# UFP.net
KiCad netlist of a schematic drawn in Altium Designer
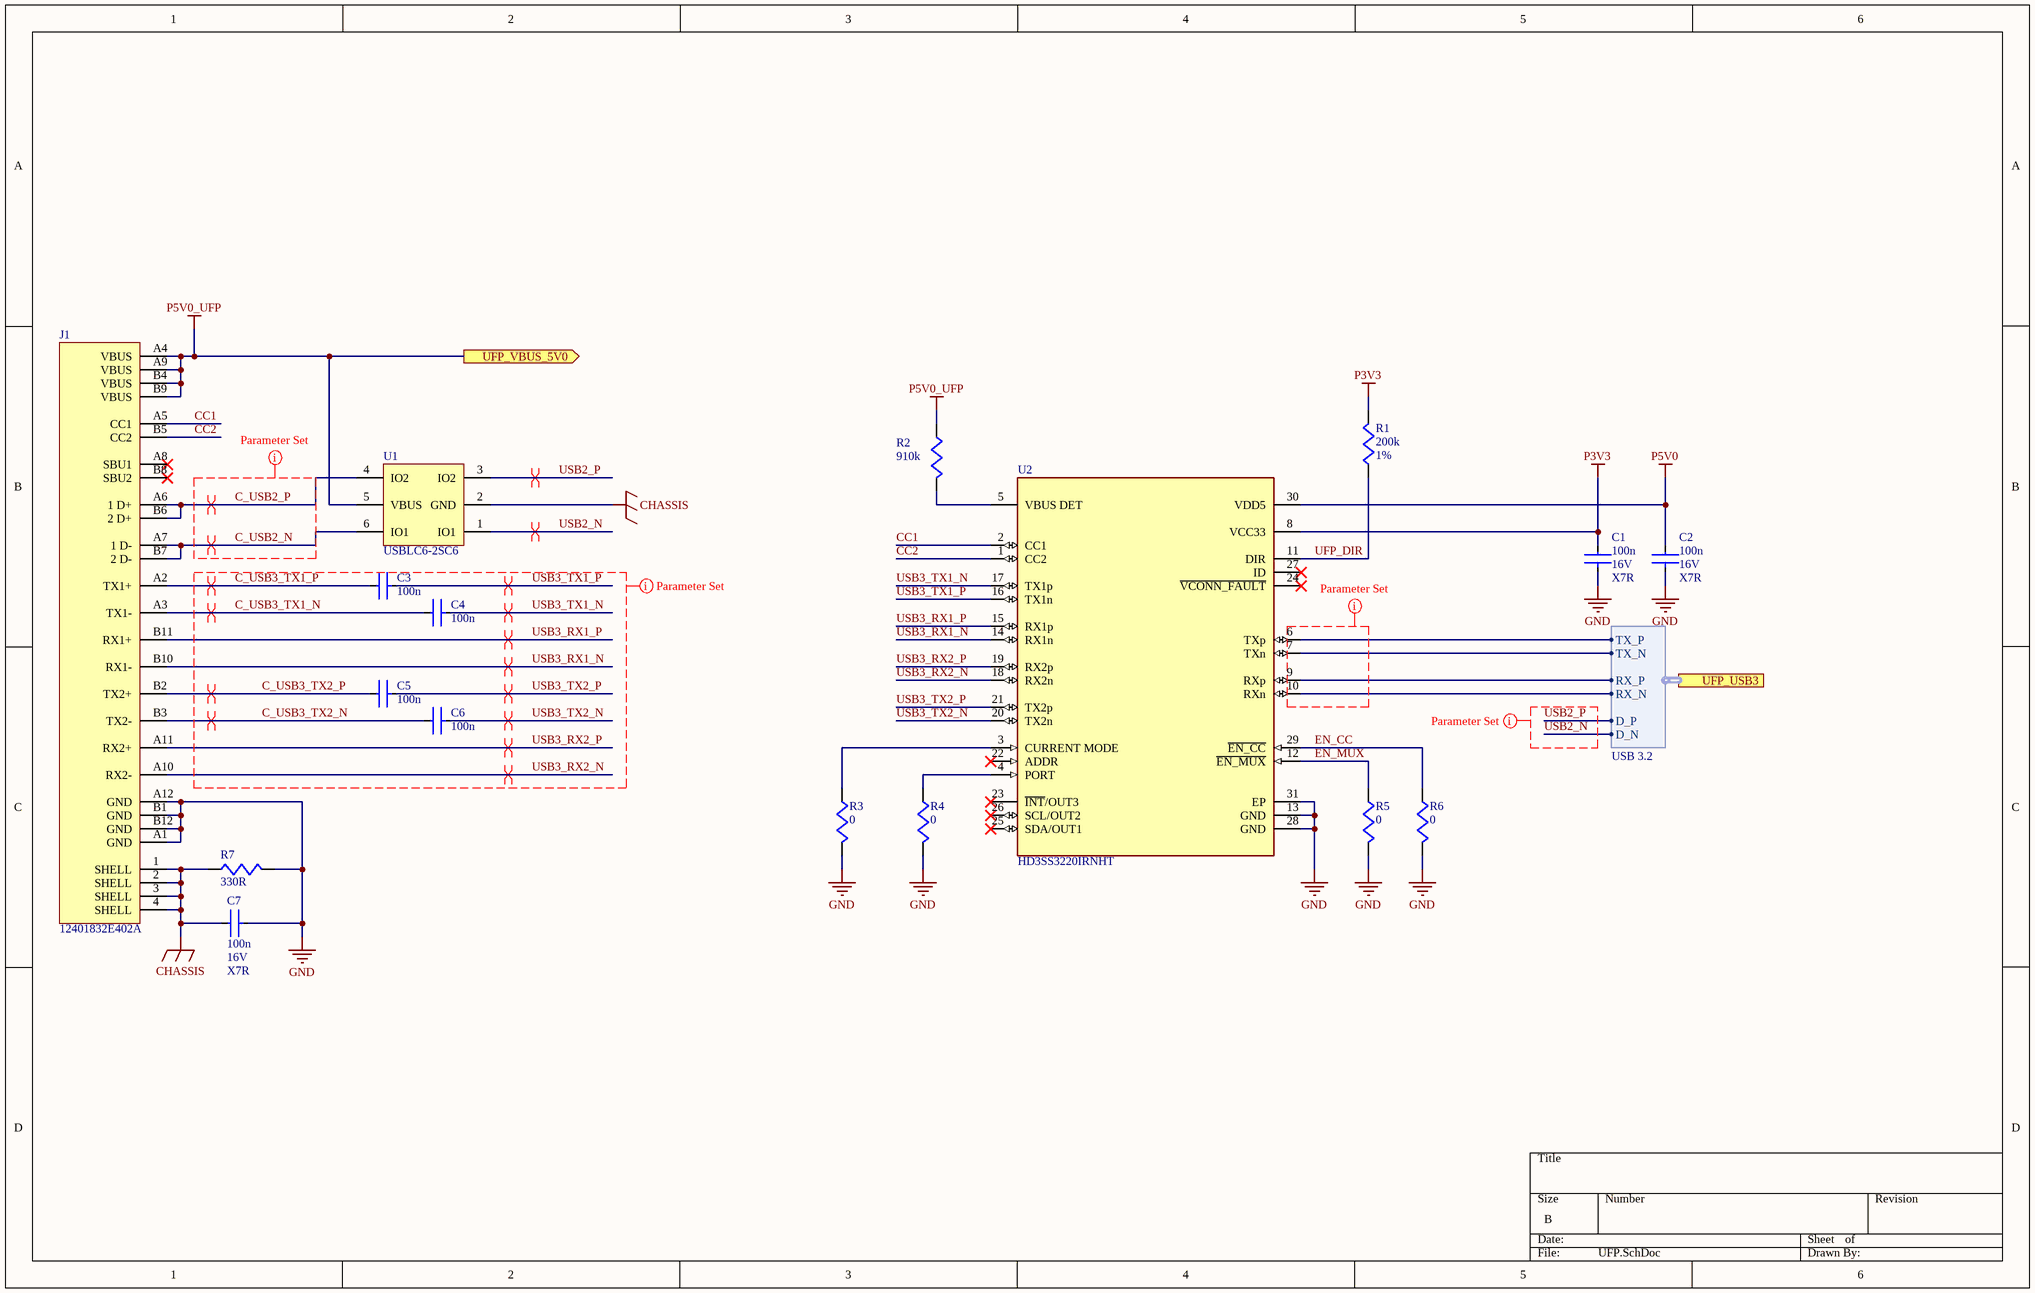
[diagram p0: UFP.SchDoc]

(export (version "E")
  (design (tool "Eeschema 10.0.6"))
  (components
    (comp (ref "C1")
      (value "100n")
      (footprint "CAPC1005X06N")
      (description "16V 100nF X7R ±10% 0402 Multilayer Ceramic Capacitors MLCC - SMD/SMT ROHS")
      (fields
        (field (name "VOLTAGE") "16V")
        (field (name "DIELECTRIC") "X7R")
        (field (name "LCSC PART #") "C1525")
        (field (name "Comment") "100nF 16V 0402")
      )
      (libsource (lib "CWRU Motorsports") (part "Capacitor"))
    )
    (comp (ref "C2")
      (value "100n")
      (footprint "CAPC1005X06N")
      (description "16V 100nF X7R ±10% 0402 Multilayer Ceramic Capacitors MLCC - SMD/SMT ROHS")
      (fields
        (field (name "VOLTAGE") "16V")
        (field (name "DIELECTRIC") "X7R")
        (field (name "LCSC PART #") "C1525")
        (field (name "Comment") "100nF 16V 0402")
      )
      (libsource (lib "CWRU Motorsports") (part "Capacitor"))
    )
    (comp (ref "C3")
      (value "100n")
      (footprint "CAPC0603X03N")
      (description "10V 100nF X5R ±10% 0201 Multilayer Ceramic Capacitors MLCC - SMD/SMT ROHS")
      (fields (field (name "VOLTAGE") "10V") (field (name "LCSC PART #") "C76934"))
      (libsource (lib "CWRU Motorsports") (part "Capacitor"))
    )
    (comp (ref "C4")
      (value "100n")
      (footprint "CAPC0603X03N")
      (description "10V 100nF X5R ±10% 0201 Multilayer Ceramic Capacitors MLCC - SMD/SMT ROHS")
      (fields (field (name "VOLTAGE") "10V") (field (name "LCSC PART #") "C76934"))
      (libsource (lib "CWRU Motorsports") (part "Capacitor"))
    )
    (comp (ref "C5")
      (value "100n")
      (footprint "CAPC0603X03N")
      (description "10V 100nF X5R ±10% 0201 Multilayer Ceramic Capacitors MLCC - SMD/SMT ROHS")
      (fields (field (name "VOLTAGE") "10V") (field (name "LCSC PART #") "C76934"))
      (libsource (lib "CWRU Motorsports") (part "Capacitor"))
    )
    (comp (ref "C6")
      (value "100n")
      (footprint "CAPC0603X03N")
      (description "10V 100nF X5R ±10% 0201 Multilayer Ceramic Capacitors MLCC - SMD/SMT ROHS")
      (fields (field (name "VOLTAGE") "10V") (field (name "LCSC PART #") "C76934"))
      (libsource (lib "CWRU Motorsports") (part "Capacitor"))
    )
    (comp (ref "C7")
      (value "100n")
      (footprint "CAPC1005X06N")
      (description "16V 100nF X7R ±10% 0402 Multilayer Ceramic Capacitors MLCC - SMD/SMT ROHS")
      (fields
        (field (name "VOLTAGE") "16V")
        (field (name "DIELECTRIC") "X7R")
        (field (name "LCSC PART #") "C1525")
        (field (name "Comment") "100nF 16V 0402")
      )
      (libsource (lib "CWRU Motorsports") (part "Capacitor"))
    )
    (comp (ref "J1")
      (value "12401832E402A")
      (footprint "FP-12401832E402A-MFG")
      (description "Conn USB Type C RCP 24 POS 0.25mm Solder RA SMD 24 Terminal 1 Port T/R")
      (fields (field (name "LCSC PART #") "C464604"))
      (libsource (lib "CWRU Motorsports") (part "50854493bfec571c3c083d899a0df29"))
    )
    (comp (ref "R1")
      (value "200k")
      (footprint "RESC1005X04M")
      (description "62.5mW Thick Film Resistors 50V ±100ppm/℃ ±1% 200kΩ 0402 Chip Resistor - Surface Mount ROHS")
      (fields
        (field (name "TOLERANCE") "1%")
        (field (name "LCSC PART #") "C114763")
        (field (name "Comment") "200k 1% 0402")
      )
      (libsource (lib "CWRU Motorsports") (part "Resistor"))
    )
    (comp (ref "R2")
      (value "910k")
      (footprint "RESC1005X04M")
      (description "62.5mW Thick Film Resistors 50V ±100ppm/℃ ±1% 910kΩ 0402 Chip Resistor - Surface Mount ROHS")
      (fields (field (name "TOLERANCE") "1%") (field (name "LCSC PART #") "C137927"))
      (libsource (lib "CWRU Motorsports") (part "Resistor"))
    )
    (comp (ref "R3")
      (value "0")
      (footprint "RESC1508X05M")
      (description "62.5mW Thick Film Resistors 50V 0Ω 0402 Chip Resistor - Surface Mount ROHS")
      (fields (field (name "TOLERANCE") "1%") (field (name "LCSC PART #") "C60485"))
      (libsource (lib "CWRU Motorsports") (part "Resistor"))
    )
    (comp (ref "R4")
      (value "0")
      (footprint "RESC1508X05M")
      (description "62.5mW Thick Film Resistors 50V 0Ω 0402 Chip Resistor - Surface Mount ROHS")
      (fields (field (name "TOLERANCE") "1%") (field (name "LCSC PART #") "C60485"))
      (libsource (lib "CWRU Motorsports") (part "Resistor"))
    )
    (comp (ref "R5")
      (value "0")
      (footprint "RESC1508X05M")
      (description "62.5mW Thick Film Resistors 50V 0Ω 0402 Chip Resistor - Surface Mount ROHS")
      (fields (field (name "TOLERANCE") "1%") (field (name "LCSC PART #") "C60485"))
      (libsource (lib "CWRU Motorsports") (part "Resistor"))
    )
    (comp (ref "R6")
      (value "0")
      (footprint "RESC1508X05M")
      (description "62.5mW Thick Film Resistors 50V 0Ω 0402 Chip Resistor - Surface Mount ROHS")
      (fields (field (name "TOLERANCE") "1%") (field (name "LCSC PART #") "C60485"))
      (libsource (lib "CWRU Motorsports") (part "Resistor"))
    )
    (comp (ref "R7")
      (value "330R")
      (footprint "RESC1005X04M")
      (description "62.5mW Thick Film Resistors 50V ±100ppm/℃ ±1% 330Ω 0402 Chip Resistor - Surface Mount ROHS")
      (fields (field (name "TOLERANCE") "1%") (field (name "LCSC PART #") "C105875"))
      (libsource (lib "CWRU Motorsports") (part "Resistor"))
    )
    (comp (ref "U1")
      (value "USBLC6-2SC6")
      (footprint "SOT95P280X145-6N")
      (description "Trans Voltage Suppressor Diode, 5V V(RWM), Unidirectional, 1 Element, Silicon")
      (fields (field (name "LCSC PART #") "C7519"))
      (libsource (lib "CWRU Motorsports") (part "USBLC6-2SC6"))
    )
    (comp (ref "U2")
      (value "HD3SS3220IRNHT")
      (footprint "FP-RNH0030A-MFG")
      (description "10-Gbps USB 3.1 Type-C 2: 1 mux with DRP Controller 30-WQFN -40 to 85")
      (fields (field (name "LCSC PART #") "C165155"))
      (libsource (lib "CWRU Motorsports") (part "bc1798bad1e85e1bff1291d9d73152b"))
    )
  )
  (nets
    (net (code "3") (name "/CC1") (class "Default")
      (node (ref "J1") (pin "A5") (pinfunction "CC1_A5") (pintype "power_in"))
      (node (ref "U2") (pin "2") (pinfunction "CC1_2") (pintype "bidirectional"))
    )
    (net (code "4") (name "/CC2") (class "Default")
      (node (ref "J1") (pin "B5") (pinfunction "CC2_B5") (pintype "power_in"))
      (node (ref "U2") (pin "1") (pinfunction "CC2_1") (pintype "bidirectional"))
    )
    (net (code "5") (name "/C_USB2_N") (class "Default")
      (node (ref "J1") (pin "A7") (pinfunction "1_D-_A7") (pintype "passive"))
      (node (ref "J1") (pin "B7") (pinfunction "2_D-_B7") (pintype "passive"))
      (node (ref "U1") (pin "6") (pinfunction "IO1_6") (pintype "passive"))
    )
    (net (code "6") (name "/C_USB2_P") (class "Default")
      (node (ref "J1") (pin "A6") (pinfunction "1_D+_A6") (pintype "passive"))
      (node (ref "J1") (pin "B6") (pinfunction "2_D+_B6") (pintype "passive"))
      (node (ref "U1") (pin "4") (pinfunction "IO2_4") (pintype "passive"))
    )
    (net (code "7") (name "/C_USB3_TX1_N") (class "Default")
      (node (ref "C4") (pin "2") (pinfunction "2_2") (pintype "passive"))
      (node (ref "J1") (pin "A3") (pinfunction "TX1-_A3") (pintype "passive"))
    )
    (net (code "8") (name "/C_USB3_TX1_P") (class "Default")
      (node (ref "C3") (pin "2") (pinfunction "2_2") (pintype "passive"))
      (node (ref "J1") (pin "A2") (pinfunction "TX1+_A2") (pintype "passive"))
    )
    (net (code "9") (name "/C_USB3_TX2_N") (class "Default")
      (node (ref "C6") (pin "2") (pinfunction "2_2") (pintype "passive"))
      (node (ref "J1") (pin "B3") (pinfunction "TX2-_B3") (pintype "passive"))
    )
    (net (code "10") (name "/C_USB3_TX2_P") (class "Default")
      (node (ref "C5") (pin "2") (pinfunction "2_2") (pintype "passive"))
      (node (ref "J1") (pin "B2") (pinfunction "TX2+_B2") (pintype "passive"))
    )
    (net (code "11") (name "/EN_CC") (class "Default")
      (node (ref "R6") (pin "1") (pinfunction "1_1") (pintype "passive"))
      (node (ref "U2") (pin "29") (pinfunction "~{EN_CC}_29") (pintype "input"))
    )
    (net (code "12") (name "/EN_MUX") (class "Default")
      (node (ref "R5") (pin "1") (pinfunction "1_1") (pintype "passive"))
      (node (ref "U2") (pin "12") (pinfunction "~{EN_MUX}_12") (pintype "input"))
    )
    (net (code "13") (name "/RX_N") (class "Default")
      (node (ref "U2") (pin "10") (pinfunction "RXn_10") (pintype "bidirectional"))
    )
    (net (code "14") (name "/RX_P") (class "Default")
      (node (ref "U2") (pin "9") (pinfunction "RXp_9") (pintype "bidirectional"))
    )
    (net (code "15") (name "/TX_N") (class "Default")
      (node (ref "U2") (pin "7") (pinfunction "TXn_7") (pintype "bidirectional"))
    )
    (net (code "16") (name "/TX_P") (class "Default")
      (node (ref "U2") (pin "6") (pinfunction "TXp_6") (pintype "bidirectional"))
    )
    (net (code "17") (name "/UFP_DIR") (class "Default")
      (node (ref "R1") (pin "1") (pinfunction "1_1") (pintype "passive"))
      (node (ref "U2") (pin "11") (pinfunction "DIR_11") (pintype "open_collector"))
    )
    (net (code "18") (name "/USB2_N") (class "Default")
      (node (ref "U1") (pin "1") (pinfunction "IO1_1") (pintype "passive"))
    )
    (net (code "19") (name "/USB2_P") (class "Default")
      (node (ref "U1") (pin "3") (pinfunction "IO2_3") (pintype "passive"))
    )
    (net (code "20") (name "/USB3_RX1_N") (class "Default")
      (node (ref "J1") (pin "B10") (pinfunction "RX1-_B10") (pintype "power_in"))
      (node (ref "U2") (pin "14") (pinfunction "RX1n_14") (pintype "bidirectional"))
    )
    (net (code "21") (name "/USB3_RX1_P") (class "Default")
      (node (ref "J1") (pin "B11") (pinfunction "RX1+_B11") (pintype "power_in"))
      (node (ref "U2") (pin "15") (pinfunction "RX1p_15") (pintype "bidirectional"))
    )
    (net (code "22") (name "/USB3_RX2_N") (class "Default")
      (node (ref "J1") (pin "A10") (pinfunction "RX2-_A10") (pintype "passive"))
      (node (ref "U2") (pin "18") (pinfunction "RX2n_18") (pintype "bidirectional"))
    )
    (net (code "23") (name "/USB3_RX2_P") (class "Default")
      (node (ref "J1") (pin "A11") (pinfunction "RX2+_A11") (pintype "passive"))
      (node (ref "U2") (pin "19") (pinfunction "RX2p_19") (pintype "bidirectional"))
    )
    (net (code "24") (name "/USB3_TX1_N") (class "Default")
      (node (ref "C4") (pin "1") (pinfunction "1_1") (pintype "passive"))
      (node (ref "U2") (pin "17") (pinfunction "TX1p_17") (pintype "bidirectional"))
    )
    (net (code "25") (name "/USB3_TX1_P") (class "Default")
      (node (ref "C3") (pin "1") (pinfunction "1_1") (pintype "passive"))
      (node (ref "U2") (pin "16") (pinfunction "TX1n_16") (pintype "bidirectional"))
    )
    (net (code "26") (name "/USB3_TX2_N") (class "Default")
      (node (ref "C6") (pin "1") (pinfunction "1_1") (pintype "passive"))
      (node (ref "U2") (pin "20") (pinfunction "TX2n_20") (pintype "bidirectional"))
    )
    (net (code "27") (name "/USB3_TX2_P") (class "Default")
      (node (ref "C5") (pin "1") (pinfunction "1_1") (pintype "passive"))
      (node (ref "U2") (pin "21") (pinfunction "TX2p_21") (pintype "bidirectional"))
    )
    (net (code "29") (name "CHASSIS") (class "Default")
      (node (ref "C7") (pin "2") (pinfunction "2_2") (pintype "passive"))
      (node (ref "J1") (pin "1") (pinfunction "SHELL_1") (pintype "power_in"))
      (node (ref "J1") (pin "2") (pinfunction "SHELL_2") (pintype "passive"))
      (node (ref "J1") (pin "3") (pinfunction "SHELL_3") (pintype "passive"))
      (node (ref "J1") (pin "4") (pinfunction "SHELL_4") (pintype "power_in"))
      (node (ref "R7") (pin "1") (pinfunction "1_1") (pintype "passive"))
      (node (ref "U1") (pin "2") (pinfunction "GND_2") (pintype "passive"))
    )
    (net (code "30") (name "GND") (class "Default")
      (node (ref "C1") (pin "1") (pinfunction "1_1") (pintype "passive"))
      (node (ref "C2") (pin "1") (pinfunction "1_1") (pintype "passive"))
      (node (ref "C7") (pin "1") (pinfunction "1_1") (pintype "passive"))
      (node (ref "J1") (pin "A1") (pinfunction "GND_A1") (pintype "passive"))
      (node (ref "J1") (pin "A12") (pinfunction "GND_A12") (pintype "power_in"))
      (node (ref "J1") (pin "B1") (pinfunction "GND_B1") (pintype "passive"))
      (node (ref "J1") (pin "B12") (pinfunction "GND_B12") (pintype "power_in"))
      (node (ref "R3") (pin "2") (pinfunction "2_2") (pintype "passive"))
      (node (ref "R4") (pin "2") (pinfunction "2_2") (pintype "passive"))
      (node (ref "R5") (pin "2") (pinfunction "2_2") (pintype "passive"))
      (node (ref "R6") (pin "2") (pinfunction "2_2") (pintype "passive"))
      (node (ref "R7") (pin "2") (pinfunction "2_2") (pintype "passive"))
      (node (ref "U2") (pin "13") (pinfunction "GND_13") (pintype "power_in"))
      (node (ref "U2") (pin "28") (pinfunction "GND_28") (pintype "power_in"))
      (node (ref "U2") (pin "31") (pinfunction "EP_31") (pintype "power_in"))
    )
    (net (code "31") (name "Net-(U2-CURRENT_MODE)") (class "Default")
      (node (ref "R3") (pin "1") (pinfunction "1_1") (pintype "passive"))
      (node (ref "U2") (pin "3") (pinfunction "CURRENT_MODE_3") (pintype "input"))
    )
    (net (code "32") (name "Net-(U2-PORT)") (class "Default")
      (node (ref "R4") (pin "1") (pinfunction "1_1") (pintype "passive"))
      (node (ref "U2") (pin "4") (pinfunction "PORT_4") (pintype "input"))
    )
    (net (code "33") (name "Net-(U2-VBUS_DET)") (class "Default")
      (node (ref "R2") (pin "2") (pinfunction "2_2") (pintype "passive"))
      (node (ref "U2") (pin "5") (pinfunction "VBUS_DET_5") (pintype "power_in"))
    )
    (net (code "34") (name "P3V3") (class "Default")
      (node (ref "C1") (pin "2") (pinfunction "2_2") (pintype "passive"))
      (node (ref "R1") (pin "2") (pinfunction "2_2") (pintype "passive"))
      (node (ref "U2") (pin "8") (pinfunction "VCC33_8") (pintype "power_in"))
    )
    (net (code "35") (name "P5V0") (class "Default")
      (node (ref "C2") (pin "2") (pinfunction "2_2") (pintype "passive"))
      (node (ref "U2") (pin "30") (pinfunction "VDD5_30") (pintype "power_in"))
    )
    (net (code "36") (name "P5V0_UFP") (class "Default")
      (node (ref "J1") (pin "A4") (pinfunction "VBUS_A4") (pintype "passive"))
      (node (ref "J1") (pin "A9") (pinfunction "VBUS_A9") (pintype "power_in"))
      (node (ref "J1") (pin "B4") (pinfunction "VBUS_B4") (pintype "passive"))
      (node (ref "J1") (pin "B9") (pinfunction "VBUS_B9") (pintype "power_in"))
      (node (ref "R2") (pin "1") (pinfunction "1_1") (pintype "passive"))
      (node (ref "U1") (pin "5") (pinfunction "VBUS_5") (pintype "passive"))
    )
    (net (code "37") (name "unconnected-(J1-SBU1-PadA8)") (class "Default")
      (node (ref "J1") (pin "A8") (pinfunction "SBU1_A8") (pintype "power_in+no_connect"))
    )
    (net (code "38") (name "unconnected-(J1-SBU2-PadB8)") (class "Default")
      (node (ref "J1") (pin "B8") (pinfunction "SBU2_B8") (pintype "power_in+no_connect"))
    )
    (net (code "39") (name "unconnected-(U2-ADDR-Pad22)") (class "Default")
      (node (ref "U2") (pin "22") (pinfunction "ADDR_22") (pintype "input+no_connect"))
    )
    (net (code "40") (name "unconnected-(U2-ID-Pad27)") (class "Default")
      (node (ref "U2") (pin "27") (pinfunction "ID_27") (pintype "open_collector+no_connect"))
    )
    (net (code "41") (name "unconnected-(U2-SCL{slash}OUT2-Pad26)") (class "Default")
      (node (ref "U2") (pin "26") (pinfunction "SCL/OUT2_26") (pintype "bidirectional+no_connect"))
    )
    (net (code "42") (name "unconnected-(U2-SDA{slash}OUT1-Pad25)") (class "Default")
      (node (ref "U2") (pin "25") (pinfunction "SDA/OUT1_25") (pintype "bidirectional+no_connect"))
    )
    (net (code "43") (name "unconnected-(U2-~{INT}{slash}OUT3-Pad23)") (class "Default")
      (node (ref "U2") (pin "23") (pinfunction "~{INT}/OUT3_23") (pintype "open_collector+no_connect"))
    )
    (net (code "44") (name "unconnected-(U2-~{VCONN_FAULT}-Pad24)") (class "Default")
      (node (ref "U2") (pin "24") (pinfunction "~{VCONN_FAULT}_24") (pintype "open_collector+no_connect"))
    )
  )
)
